# design.net
KiCad netlist of a schematic drawn in Altium Designer
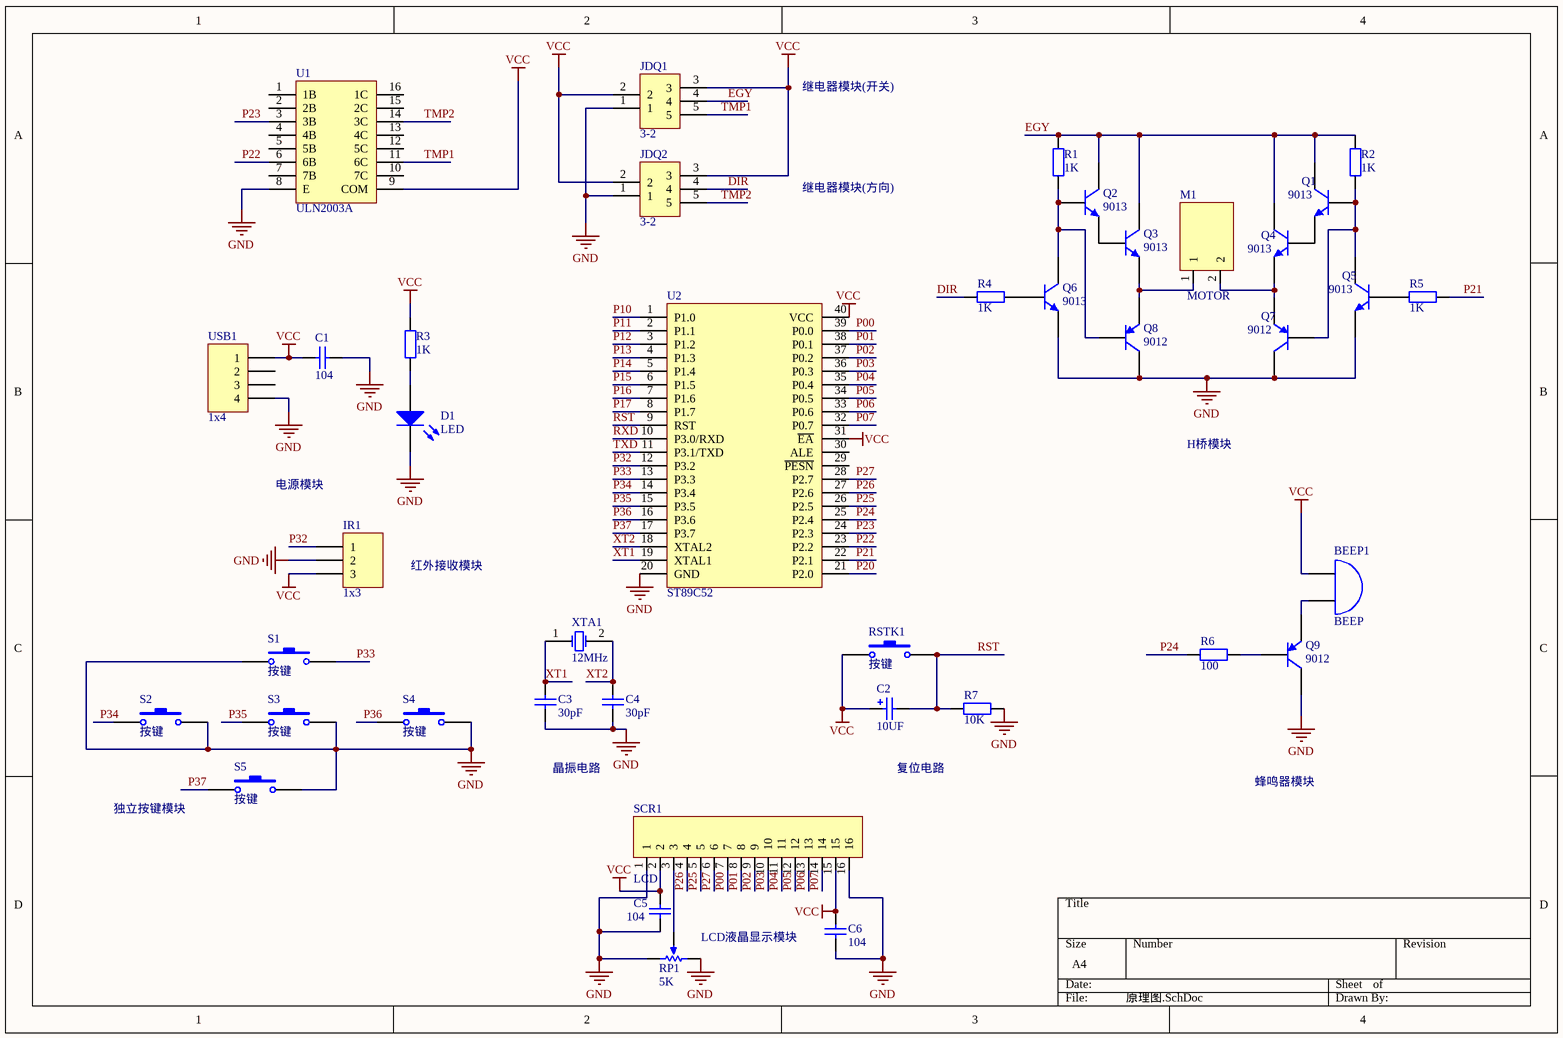
[diagram p0: 原理图.SchDoc]

(export (version "E")
  (design (tool "Eeschema 10.0.6"))
  (components
    (comp (ref "BEEP1") (value "BEEP") (footprint "BEEP") (libsource (lib "例程原理图库") (part "蜂鸣器")))
    (comp (ref "C1") (value "104") (footprint "CAP") (libsource (lib "例程原理图库") (part "瓷片电容")))
    (comp (ref "C2") (value "10UF") (footprint "CAP-ELEC") (libsource (lib "例程原理图库") (part "电解电容")))
    (comp (ref "C3") (value "30pF") (footprint "CAP") (libsource (lib "例程原理图库") (part "瓷片电容")))
    (comp (ref "C4") (value "30pF") (footprint "CAP") (libsource (lib "例程原理图库") (part "瓷片电容")))
    (comp (ref "C5") (value "104") (footprint "CAP") (libsource (lib "例程原理图库") (part "瓷片电容")))
    (comp (ref "C6") (value "104") (footprint "CAP") (libsource (lib "例程原理图库") (part "瓷片电容")))
    (comp (ref "D1") (value "LED") (footprint "LED") (libsource (lib "例程原理图库") (part "LED")))
    (comp (ref "IR1") (value "1x3") (footprint "RAY") (libsource (lib "例程原理图库") (part "1x3")))
    (comp (ref "JDQ1") (value "3-2") (footprint "RELAY") (libsource (lib "原理图库") (part "RELAY")))
    (comp (ref "JDQ2") (value "3-2") (footprint "RELAY") (libsource (lib "原理图库") (part "RELAY")))
    (comp (ref "M1") (value "MOTOR") (footprint "MOTOR") (libsource (lib "原理图库") (part "MOTOR")))
    (comp (ref "Q1") (value "9013") (footprint "PINS-3") (libsource (lib "例程原理图库") (part "NPN")))
    (comp (ref "Q2") (value "9013") (footprint "PINS-3") (libsource (lib "例程原理图库") (part "NPN")))
    (comp (ref "Q3") (value "9013") (footprint "PINS-3") (libsource (lib "例程原理图库") (part "NPN")))
    (comp (ref "Q4") (value "9013") (footprint "PINS-3") (libsource (lib "例程原理图库") (part "NPN")))
    (comp (ref "Q5") (value "9013") (footprint "PINS-3") (libsource (lib "例程原理图库") (part "NPN")))
    (comp (ref "Q6") (value "9013") (footprint "PINS-3") (libsource (lib "例程原理图库") (part "NPN")))
    (comp (ref "Q7") (value "9012") (footprint "PINS-3") (libsource (lib "例程原理图库") (part "PNP")))
    (comp (ref "Q8") (value "9012") (footprint "PINS-3") (libsource (lib "例程原理图库") (part "PNP")))
    (comp (ref "Q9") (value "9012") (footprint "PINS-3") (libsource (lib "原理图库") (part "PNP")))
    (comp (ref "R1") (value "1K") (footprint "RES") (libsource (lib "") (part "电阻_1")))
    (comp (ref "R2") (value "1K") (footprint "RES") (libsource (lib "") (part "电阻_2")))
    (comp (ref "R3") (value "1K") (footprint "RES") (libsource (lib "") (part "电阻_1")))
    (comp (ref "R4") (value "1K") (footprint "RES") (libsource (lib "例程原理图库") (part "电阻")))
    (comp (ref "R5") (value "1K") (footprint "RES") (libsource (lib "") (part "电阻_1")))
    (comp (ref "R6") (value "100") (footprint "RES") (libsource (lib "例程原理图库") (part "电阻")))
    (comp (ref "R7") (value "10K") (footprint "RES") (libsource (lib "") (part "电阻_2")))
    (comp (ref "RP1") (value "5K") (footprint "RES-ADJ") (libsource (lib "例程原理图库") (part "可调电阻")))
    (comp (ref "RSTK1") (value "按键") (footprint "KEY-4") (libsource (lib "例程原理图库") (part "按键")))
    (comp (ref "S1") (value "按键") (footprint "KEY-4") (libsource (lib "例程原理图库") (part "按键")))
    (comp (ref "S2") (value "按键") (footprint "KEY-4") (libsource (lib "例程原理图库") (part "按键")))
    (comp (ref "S3") (value "按键") (footprint "KEY-4") (libsource (lib "例程原理图库") (part "按键")))
    (comp (ref "S4") (value "按键") (footprint "KEY-4") (libsource (lib "例程原理图库") (part "按键")))
    (comp (ref "S5") (value "按键") (footprint "KEY-4") (libsource (lib "例程原理图库") (part "按键")))
    (comp (ref "SCR1") (value "LCD") (footprint "LCD") (libsource (lib "原理图库") (part "LCD")))
    (comp (ref "U1") (value "ULN2003A") (footprint "DIP16") (libsource (lib "原理图库") (part "ULN2003A")))
    (comp (ref "U2") (value "ST89C52") (footprint "STC89C52") (libsource (lib "例程原理图库") (part "STC89C52")))
    (comp (ref "USB1") (value "1x4") (footprint "USB") (libsource (lib "例程原理图库") (part "1x4")))
    (comp (ref "XTA1") (value "12MHz") (footprint "CRYSTAL") (libsource (lib "例程原理图库") (part "晶振")))
  )
  (nets
    (net (code "1") (name "/DIR") (class "Default")
      (node (ref "JDQ2") (pin "4") (pinfunction "4_4") (pintype "passive"))
      (node (ref "R4") (pin "1") (pinfunction "1_1") (pintype "passive"))
    )
    (net (code "2") (name "/EGY") (class "Default")
      (node (ref "JDQ1") (pin "4") (pinfunction "4_4") (pintype "passive"))
      (node (ref "Q1") (pin "1") (pinfunction "C_1") (pintype "passive"))
      (node (ref "Q2") (pin "1") (pinfunction "C_1") (pintype "passive"))
      (node (ref "Q3") (pin "1") (pinfunction "C_1") (pintype "passive"))
      (node (ref "Q4") (pin "1") (pinfunction "C_1") (pintype "passive"))
      (node (ref "R1") (pin "1") (pinfunction "1_1") (pintype "passive"))
      (node (ref "R2") (pin "1") (pinfunction "1_1") (pintype "passive"))
    )
    (net (code "3") (name "/P00") (class "Default")
      (node (ref "SCR1") (pin "7") (pinfunction "7_7") (pintype "passive"))
      (node (ref "U2") (pin "39") (pinfunction "P0.0_39") (pintype "passive"))
    )
    (net (code "4") (name "/P01") (class "Default")
      (node (ref "SCR1") (pin "8") (pinfunction "8_8") (pintype "passive"))
      (node (ref "U2") (pin "38") (pinfunction "P0.1_38") (pintype "passive"))
    )
    (net (code "5") (name "/P02") (class "Default")
      (node (ref "SCR1") (pin "9") (pinfunction "9_9") (pintype "passive"))
      (node (ref "U2") (pin "37") (pinfunction "P0.2_37") (pintype "passive"))
    )
    (net (code "6") (name "/P03") (class "Default")
      (node (ref "SCR1") (pin "10") (pinfunction "10_10") (pintype "passive"))
      (node (ref "U2") (pin "36") (pinfunction "P0.3_36") (pintype "passive"))
    )
    (net (code "7") (name "/P04") (class "Default")
      (node (ref "SCR1") (pin "11") (pinfunction "11_11") (pintype "passive"))
      (node (ref "U2") (pin "35") (pinfunction "P0.4_35") (pintype "passive"))
    )
    (net (code "8") (name "/P05") (class "Default")
      (node (ref "SCR1") (pin "12") (pinfunction "12_12") (pintype "passive"))
      (node (ref "U2") (pin "34") (pinfunction "P0.5_34") (pintype "passive"))
    )
    (net (code "9") (name "/P06") (class "Default")
      (node (ref "SCR1") (pin "13") (pinfunction "13_13") (pintype "passive"))
      (node (ref "U2") (pin "33") (pinfunction "P0.6_33") (pintype "passive"))
    )
    (net (code "10") (name "/P07") (class "Default")
      (node (ref "SCR1") (pin "14") (pinfunction "14_14") (pintype "passive"))
      (node (ref "U2") (pin "32") (pinfunction "P0.7_32") (pintype "passive"))
    )
    (net (code "11") (name "/P10") (class "Default")
      (node (ref "U2") (pin "1") (pinfunction "P1.0_1") (pintype "passive"))
    )
    (net (code "12") (name "/P11") (class "Default")
      (node (ref "U2") (pin "2") (pinfunction "P1.1_2") (pintype "passive"))
    )
    (net (code "13") (name "/P12") (class "Default")
      (node (ref "U2") (pin "3") (pinfunction "P1.2_3") (pintype "passive"))
    )
    (net (code "14") (name "/P13") (class "Default")
      (node (ref "U2") (pin "4") (pinfunction "P1.3_4") (pintype "passive"))
    )
    (net (code "15") (name "/P14") (class "Default")
      (node (ref "U2") (pin "5") (pinfunction "P1.4_5") (pintype "passive"))
    )
    (net (code "16") (name "/P15") (class "Default")
      (node (ref "U2") (pin "6") (pinfunction "P1.5_6") (pintype "passive"))
    )
    (net (code "17") (name "/P16") (class "Default")
      (node (ref "U2") (pin "7") (pinfunction "P1.6_7") (pintype "passive"))
    )
    (net (code "18") (name "/P17") (class "Default")
      (node (ref "U2") (pin "8") (pinfunction "P1.7_8") (pintype "passive"))
    )
    (net (code "19") (name "/P20") (class "Default")
      (node (ref "U2") (pin "21") (pinfunction "P2.0_21") (pintype "passive"))
    )
    (net (code "20") (name "/P21") (class "Default")
      (node (ref "R5") (pin "1") (pinfunction "1_1") (pintype "passive"))
      (node (ref "U2") (pin "22") (pinfunction "P2.1_22") (pintype "passive"))
    )
    (net (code "21") (name "/P22") (class "Default")
      (node (ref "U1") (pin "6") (pinfunction "6B_6") (pintype "passive"))
      (node (ref "U2") (pin "23") (pinfunction "P2.2_23") (pintype "passive"))
    )
    (net (code "22") (name "/P23") (class "Default")
      (node (ref "U1") (pin "3") (pinfunction "3B_3") (pintype "passive"))
      (node (ref "U2") (pin "24") (pinfunction "P2.3_24") (pintype "passive"))
    )
    (net (code "23") (name "/P24") (class "Default")
      (node (ref "R6") (pin "1") (pinfunction "1_1") (pintype "passive"))
      (node (ref "U2") (pin "25") (pinfunction "P2.4_25") (pintype "passive"))
    )
    (net (code "24") (name "/P25") (class "Default")
      (node (ref "SCR1") (pin "5") (pinfunction "5_5") (pintype "passive"))
      (node (ref "U2") (pin "26") (pinfunction "P2.5_26") (pintype "passive"))
    )
    (net (code "25") (name "/P26") (class "Default")
      (node (ref "SCR1") (pin "4") (pinfunction "4_4") (pintype "passive"))
      (node (ref "U2") (pin "27") (pinfunction "P2.6_27") (pintype "passive"))
    )
    (net (code "26") (name "/P27") (class "Default")
      (node (ref "SCR1") (pin "6") (pinfunction "6_6") (pintype "passive"))
      (node (ref "U2") (pin "28") (pinfunction "P2.7_28") (pintype "passive"))
    )
    (net (code "27") (name "/P32") (class "Default")
      (node (ref "IR1") (pin "1") (pinfunction "1_1") (pintype "passive"))
      (node (ref "U2") (pin "12") (pinfunction "P3.2_12") (pintype "passive"))
    )
    (net (code "28") (name "/P33") (class "Default")
      (node (ref "S1") (pin "2") (pinfunction "2_2") (pintype "passive"))
      (node (ref "U2") (pin "13") (pinfunction "P3.3_13") (pintype "passive"))
    )
    (net (code "29") (name "/P34") (class "Default")
      (node (ref "S2") (pin "1") (pinfunction "1_1") (pintype "passive"))
      (node (ref "U2") (pin "14") (pinfunction "P3.4_14") (pintype "passive"))
    )
    (net (code "30") (name "/P35") (class "Default")
      (node (ref "S3") (pin "1") (pinfunction "1_1") (pintype "passive"))
      (node (ref "U2") (pin "15") (pinfunction "P3.5_15") (pintype "passive"))
    )
    (net (code "31") (name "/P36") (class "Default")
      (node (ref "S4") (pin "1") (pinfunction "1_1") (pintype "passive"))
      (node (ref "U2") (pin "16") (pinfunction "P3.6_16") (pintype "passive"))
    )
    (net (code "32") (name "/P37") (class "Default")
      (node (ref "S5") (pin "1") (pinfunction "1_1") (pintype "passive"))
      (node (ref "U2") (pin "17") (pinfunction "P3.7_17") (pintype "passive"))
    )
    (net (code "33") (name "/RST") (class "Default")
      (node (ref "C2") (pin "2") (pinfunction "2_2") (pintype "passive"))
      (node (ref "R7") (pin "2") (pinfunction "2_2") (pintype "passive"))
      (node (ref "RSTK1") (pin "2") (pinfunction "2_2") (pintype "passive"))
      (node (ref "U2") (pin "9") (pinfunction "RST_9") (pintype "passive"))
    )
    (net (code "34") (name "/RXD") (class "Default")
      (node (ref "U2") (pin "10") (pinfunction "P3.0/RXD_10") (pintype "passive"))
    )
    (net (code "35") (name "/TMP1") (class "Default")
      (node (ref "JDQ1") (pin "5") (pinfunction "5_5") (pintype "passive"))
      (node (ref "U1") (pin "11") (pinfunction "6C_11") (pintype "passive"))
    )
    (net (code "36") (name "/TMP2") (class "Default")
      (node (ref "JDQ2") (pin "5") (pinfunction "5_5") (pintype "passive"))
      (node (ref "U1") (pin "14") (pinfunction "3C_14") (pintype "passive"))
    )
    (net (code "37") (name "/TXD") (class "Default")
      (node (ref "U2") (pin "11") (pinfunction "P3.1/TXD_11") (pintype "passive"))
    )
    (net (code "38") (name "/XT1") (class "Default")
      (node (ref "C3") (pin "2") (pinfunction "2_2") (pintype "passive"))
      (node (ref "U2") (pin "19") (pinfunction "XTAL1_19") (pintype "passive"))
      (node (ref "XTA1") (pin "1") (pinfunction "OSC1_1") (pintype "passive"))
    )
    (net (code "39") (name "/XT2") (class "Default")
      (node (ref "C4") (pin "2") (pinfunction "2_2") (pintype "passive"))
      (node (ref "U2") (pin "18") (pinfunction "XTAL2_18") (pintype "passive"))
      (node (ref "XTA1") (pin "2") (pinfunction "OSC2_2") (pintype "passive"))
    )
    (net (code "40") (name "GND") (class "Default")
      (node (ref "C1") (pin "1") (pinfunction "1_1") (pintype "passive"))
      (node (ref "C3") (pin "1") (pinfunction "1_1") (pintype "passive"))
      (node (ref "C4") (pin "1") (pinfunction "1_1") (pintype "passive"))
      (node (ref "C5") (pin "1") (pinfunction "1_1") (pintype "passive"))
      (node (ref "C6") (pin "1") (pinfunction "1_1") (pintype "passive"))
      (node (ref "D1") (pin "2") (pinfunction "K_2") (pintype "passive"))
      (node (ref "IR1") (pin "2") (pinfunction "2_2") (pintype "passive"))
      (node (ref "JDQ1") (pin "1") (pinfunction "1_1") (pintype "passive"))
      (node (ref "JDQ2") (pin "1") (pinfunction "1_1") (pintype "passive"))
      (node (ref "Q5") (pin "3") (pinfunction "E_3") (pintype "passive"))
      (node (ref "Q6") (pin "3") (pinfunction "E_3") (pintype "passive"))
      (node (ref "Q7") (pin "3") (pinfunction "C_3") (pintype "passive"))
      (node (ref "Q8") (pin "3") (pinfunction "C_3") (pintype "passive"))
      (node (ref "Q9") (pin "3") (pinfunction "C_3") (pintype "passive"))
      (node (ref "R7") (pin "1") (pinfunction "1_1") (pintype "passive"))
      (node (ref "RP1") (pin "1") (pinfunction "TOP_1") (pintype "passive"))
      (node (ref "RP1") (pin "3") (pinfunction "BOT_3") (pintype "passive"))
      (node (ref "S1") (pin "1") (pinfunction "1_1") (pintype "passive"))
      (node (ref "S2") (pin "2") (pinfunction "2_2") (pintype "passive"))
      (node (ref "S3") (pin "2") (pinfunction "2_2") (pintype "passive"))
      (node (ref "S4") (pin "2") (pinfunction "2_2") (pintype "passive"))
      (node (ref "S5") (pin "2") (pinfunction "2_2") (pintype "passive"))
      (node (ref "SCR1") (pin "1") (pinfunction "1_1") (pintype "passive"))
      (node (ref "SCR1") (pin "16") (pinfunction "16_16") (pintype "passive"))
      (node (ref "U1") (pin "8") (pinfunction "E_8") (pintype "passive"))
      (node (ref "U2") (pin "20") (pinfunction "GND_20") (pintype "passive"))
      (node (ref "USB1") (pin "4") (pinfunction "4_4") (pintype "passive"))
    )
    (net (code "41") (name "Net-(BEEP1-B)") (class "Default")
      (node (ref "BEEP1") (pin "2") (pinfunction "B_2") (pintype "passive"))
      (node (ref "Q9") (pin "1") (pinfunction "E_1") (pintype "passive"))
    )
    (net (code "42") (name "Net-(D1-A)") (class "Default")
      (node (ref "D1") (pin "1") (pinfunction "A_1") (pintype "passive"))
      (node (ref "R3") (pin "2") (pinfunction "2_2") (pintype "passive"))
    )
    (net (code "43") (name "Net-(Q1-B)") (class "Default")
      (node (ref "Q1") (pin "2") (pinfunction "B_2") (pintype "passive"))
      (node (ref "Q5") (pin "1") (pinfunction "C_1") (pintype "passive"))
      (node (ref "Q7") (pin "2") (pinfunction "B_2") (pintype "passive"))
      (node (ref "R2") (pin "2") (pinfunction "2_2") (pintype "passive"))
    )
    (net (code "44") (name "Net-(Q1-E)") (class "Default")
      (node (ref "Q1") (pin "3") (pinfunction "E_3") (pintype "passive"))
      (node (ref "Q4") (pin "2") (pinfunction "B_2") (pintype "passive"))
    )
    (net (code "45") (name "Net-(Q2-B)") (class "Default")
      (node (ref "Q2") (pin "2") (pinfunction "B_2") (pintype "passive"))
      (node (ref "Q6") (pin "1") (pinfunction "C_1") (pintype "passive"))
      (node (ref "Q8") (pin "2") (pinfunction "B_2") (pintype "passive"))
      (node (ref "R1") (pin "2") (pinfunction "2_2") (pintype "passive"))
    )
    (net (code "46") (name "Net-(Q2-E)") (class "Default")
      (node (ref "Q2") (pin "3") (pinfunction "E_3") (pintype "passive"))
      (node (ref "Q3") (pin "2") (pinfunction "B_2") (pintype "passive"))
    )
    (net (code "47") (name "Net-(Q3-E)") (class "Default")
      (node (ref "M1") (pin "1") (pinfunction "1_1") (pintype "passive"))
      (node (ref "Q3") (pin "3") (pinfunction "E_3") (pintype "passive"))
      (node (ref "Q8") (pin "1") (pinfunction "E_1") (pintype "passive"))
    )
    (net (code "48") (name "Net-(Q4-E)") (class "Default")
      (node (ref "M1") (pin "2") (pinfunction "2_2") (pintype "passive"))
      (node (ref "Q4") (pin "3") (pinfunction "E_3") (pintype "passive"))
      (node (ref "Q7") (pin "1") (pinfunction "E_1") (pintype "passive"))
    )
    (net (code "49") (name "Net-(Q5-B)") (class "Default")
      (node (ref "Q5") (pin "2") (pinfunction "B_2") (pintype "passive"))
      (node (ref "R5") (pin "2") (pinfunction "2_2") (pintype "passive"))
    )
    (net (code "50") (name "Net-(Q6-B)") (class "Default")
      (node (ref "Q6") (pin "2") (pinfunction "B_2") (pintype "passive"))
      (node (ref "R4") (pin "2") (pinfunction "2_2") (pintype "passive"))
    )
    (net (code "51") (name "Net-(Q9-B)") (class "Default")
      (node (ref "Q9") (pin "2") (pinfunction "B_2") (pintype "passive"))
      (node (ref "R6") (pin "2") (pinfunction "2_2") (pintype "passive"))
    )
    (net (code "52") (name "Net-(RP1-TAP)") (class "Default")
      (node (ref "RP1") (pin "2") (pinfunction "TAP_2") (pintype "passive"))
      (node (ref "SCR1") (pin "3") (pinfunction "3_3") (pintype "passive"))
    )
    (net (code "53") (name "VCC") (class "Default")
      (node (ref "BEEP1") (pin "1") (pinfunction "A_1") (pintype "passive"))
      (node (ref "C1") (pin "2") (pinfunction "2_2") (pintype "passive"))
      (node (ref "C2") (pin "1") (pinfunction "1_1") (pintype "passive"))
      (node (ref "C5") (pin "2") (pinfunction "2_2") (pintype "passive"))
      (node (ref "C6") (pin "2") (pinfunction "2_2") (pintype "passive"))
      (node (ref "IR1") (pin "3") (pinfunction "3_3") (pintype "passive"))
      (node (ref "JDQ1") (pin "2") (pinfunction "2_2") (pintype "passive"))
      (node (ref "JDQ1") (pin "3") (pinfunction "3_3") (pintype "passive"))
      (node (ref "JDQ2") (pin "2") (pinfunction "2_2") (pintype "passive"))
      (node (ref "JDQ2") (pin "3") (pinfunction "3_3") (pintype "passive"))
      (node (ref "R3") (pin "1") (pinfunction "1_1") (pintype "passive"))
      (node (ref "RSTK1") (pin "1") (pinfunction "1_1") (pintype "passive"))
      (node (ref "SCR1") (pin "15") (pinfunction "15_15") (pintype "passive"))
      (node (ref "SCR1") (pin "2") (pinfunction "2_2") (pintype "passive"))
      (node (ref "U1") (pin "9") (pinfunction "COM_9") (pintype "passive"))
      (node (ref "U2") (pin "31") (pinfunction "~{EA}_31") (pintype "passive"))
      (node (ref "U2") (pin "40") (pinfunction "VCC_40") (pintype "passive"))
      (node (ref "USB1") (pin "1") (pinfunction "1_1") (pintype "passive"))
    )
    (net (code "54") (name "unconnected-(U1-1B-Pad1)") (class "Default")
      (node (ref "U1") (pin "1") (pinfunction "1B_1") (pintype "passive"))
    )
    (net (code "55") (name "unconnected-(U1-1C-Pad16)") (class "Default")
      (node (ref "U1") (pin "16") (pinfunction "1C_16") (pintype "passive"))
    )
    (net (code "56") (name "unconnected-(U1-2B-Pad2)") (class "Default")
      (node (ref "U1") (pin "2") (pinfunction "2B_2") (pintype "passive"))
    )
    (net (code "57") (name "unconnected-(U1-2C-Pad15)") (class "Default")
      (node (ref "U1") (pin "15") (pinfunction "2C_15") (pintype "passive"))
    )
    (net (code "58") (name "unconnected-(U1-4B-Pad4)") (class "Default")
      (node (ref "U1") (pin "4") (pinfunction "4B_4") (pintype "passive"))
    )
    (net (code "59") (name "unconnected-(U1-4C-Pad13)") (class "Default")
      (node (ref "U1") (pin "13") (pinfunction "4C_13") (pintype "passive"))
    )
    (net (code "60") (name "unconnected-(U1-5B-Pad5)") (class "Default")
      (node (ref "U1") (pin "5") (pinfunction "5B_5") (pintype "passive"))
    )
    (net (code "61") (name "unconnected-(U1-5C-Pad12)") (class "Default")
      (node (ref "U1") (pin "12") (pinfunction "5C_12") (pintype "passive"))
    )
    (net (code "62") (name "unconnected-(U1-7B-Pad7)") (class "Default")
      (node (ref "U1") (pin "7") (pinfunction "7B_7") (pintype "passive"))
    )
    (net (code "63") (name "unconnected-(U1-7C-Pad10)") (class "Default")
      (node (ref "U1") (pin "10") (pinfunction "7C_10") (pintype "passive"))
    )
    (net (code "64") (name "unconnected-(U2-ALE-Pad30)") (class "Default")
      (node (ref "U2") (pin "30") (pinfunction "ALE_30") (pintype "passive"))
    )
    (net (code "65") (name "unconnected-(U2-~{PESN}-Pad29)") (class "Default")
      (node (ref "U2") (pin "29") (pinfunction "~{PESN}_29") (pintype "passive"))
    )
    (net (code "66") (name "unconnected-(USB1-Pad2)") (class "Default")
      (node (ref "USB1") (pin "2") (pinfunction "2_2") (pintype "passive"))
    )
    (net (code "67") (name "unconnected-(USB1-Pad3)") (class "Default")
      (node (ref "USB1") (pin "3") (pinfunction "3_3") (pintype "passive"))
    )
  )
)
